# Vref.net
KiCad netlist of a schematic drawn in Altium Designer
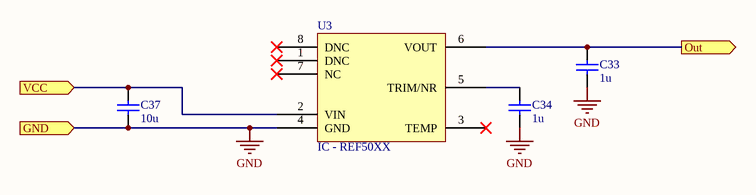
[diagram p0: Vref.SchDoc]

(export (version "E")
  (design (tool "Eeschema 10.0.6"))
  (components
    (comp (ref "C33")
      (value "1u")
      (footprint "CS-0603")
      (fields
        (field (name "TOLERANCE") "10%")
        (field (name "VOLTAGE") "16V")
        (field (name "Comment") "CS - CAPACITOR")
      )
      (libsource (lib "CHINOOK_LIBRARY") (part "CS - CAPACITOR"))
    )
    (comp (ref "C34")
      (value "1u")
      (footprint "CS-0603")
      (fields
        (field (name "TOLERANCE") "10%")
        (field (name "VOLTAGE") "16V")
        (field (name "Comment") "CS - CAPACITOR")
      )
      (libsource (lib "CHINOOK_LIBRARY") (part "CS - CAPACITOR"))
    )
    (comp (ref "C37")
      (value "10u")
      (footprint "CS-0603")
      (fields
        (field (name "TOLERANCE") "10%")
        (field (name "VOLTAGE") "16V")
        (field (name "Comment") "CS - CAPACITOR")
      )
      (libsource (lib "CHINOOK_LIBRARY") (part "CS - CAPACITOR"))
    )
    (comp (ref "U3")
      (value "IC - REF50XX")
      (footprint "IC-SOIC-8")
      (description "VOLTAGE REFERENCE")
      (libsource (lib "CHINOOK_LIBRARY") (part "IC - REF50XX"))
    )
  )
  (nets
    (net (code "1") (name "/Out") (class "Default")
      (node (ref "C33") (pin "2") (pinfunction "2_2") (pintype "passive"))
      (node (ref "U3") (pin "6") (pinfunction "VOUT_6") (pintype "passive"))
    )
    (net (code "2") (name "/VCC") (class "Default")
      (node (ref "C37") (pin "2") (pinfunction "2_2") (pintype "passive"))
      (node (ref "U3") (pin "2") (pinfunction "VIN_2") (pintype "passive"))
    )
    (net (code "3") (name "GND") (class "Default")
      (node (ref "C33") (pin "1") (pinfunction "1_1") (pintype "passive"))
      (node (ref "C34") (pin "1") (pinfunction "1_1") (pintype "passive"))
      (node (ref "C37") (pin "1") (pinfunction "1_1") (pintype "passive"))
      (node (ref "U3") (pin "4") (pinfunction "GND_4") (pintype "passive"))
    )
    (net (code "4") (name "Net-(U3-TRIM{slash}NR)") (class "Default")
      (node (ref "C34") (pin "2") (pinfunction "2_2") (pintype "passive"))
      (node (ref "U3") (pin "5") (pinfunction "TRIM/NR_5") (pintype "passive"))
    )
    (net (code "5") (name "unconnected-(U3-DNC-Pad1)") (class "Default")
      (node (ref "U3") (pin "1") (pinfunction "DNC_1") (pintype "passive+no_connect"))
    )
    (net (code "6") (name "unconnected-(U3-DNC-Pad8)") (class "Default")
      (node (ref "U3") (pin "8") (pinfunction "DNC_8") (pintype "passive+no_connect"))
    )
    (net (code "7") (name "unconnected-(U3-NC-Pad7)") (class "Default")
      (node (ref "U3") (pin "7") (pinfunction "NC_7") (pintype "passive+no_connect"))
    )
    (net (code "8") (name "unconnected-(U3-TEMP-Pad3)") (class "Default")
      (node (ref "U3") (pin "3") (pinfunction "TEMP_3") (pintype "passive+no_connect"))
    )
  )
)
